# D_amp_Schem.net
KiCad netlist of a schematic drawn in Altium Designer
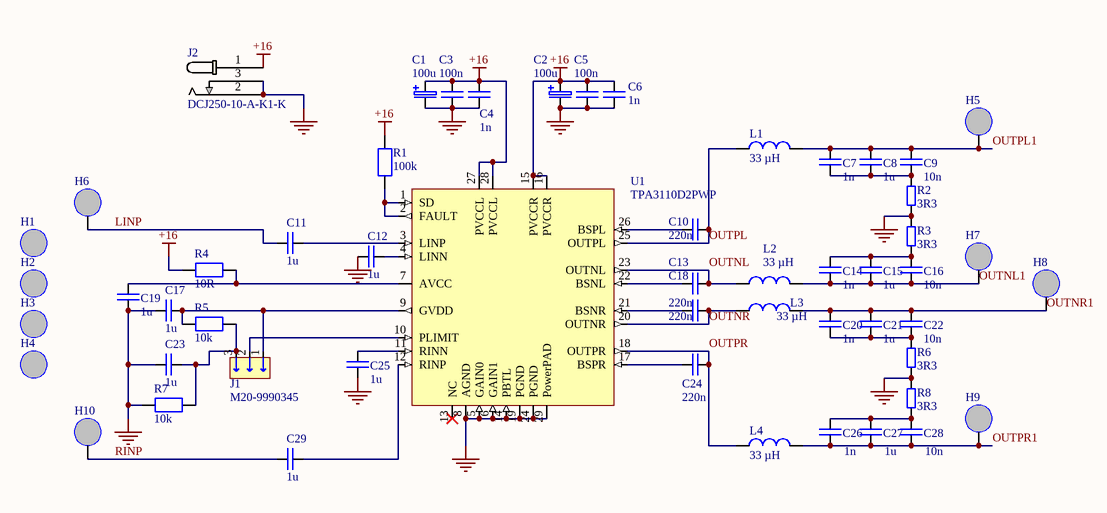
[diagram p0: D_amp_Schem.SchDoc]

(export (version "E")
  (design (tool "Eeschema 10.0.6"))
  (components
    (comp (ref "C1")
      (value "100u")
      (footprint "Cap_100u_Alum")
      (description "CAP ALUM 100UF 20% 50V SMD")
      (fields
        (field (name "MANUFACTURER") "United Chemi-Con")
        (field (name "MANUFACTURER PART NUMBER") "EMZR500ARA101MF80G")
      )
      (libsource (lib "Schematic_Library") (part "Cap_100u_Alum"))
    )
    (comp (ref "C2")
      (value "100u")
      (footprint "Cap_100u_Alum")
      (description "CAP ALUM 100UF 20% 50V SMD")
      (fields
        (field (name "MANUFACTURER") "United Chemi-Con")
        (field (name "MANUFACTURER PART NUMBER") "EMZR500ARA101MF80G")
      )
      (libsource (lib "Schematic_Library") (part "Cap_100u_Alum"))
    )
    (comp (ref "C3")
      (value "100n")
      (footprint "Cap_0603")
      (description "CAP CER 0.1UF 50V X7R 0603")
      (fields
        (field (name "MANUFACTURER") "KEMET")
        (field (name "MANUFACTURER PART NUMBER") "C0603C104K5RACTU")
      )
      (libsource (lib "Schematic_Library") (part "Cap_100n_0603_cer"))
    )
    (comp (ref "C4")
      (value "1n")
      (footprint "Cap_0603")
      (description "CAP CER 1000PF 50V X7R 0603")
      (fields
        (field (name "MANUFACTURER") "KEMET")
        (field (name "MANUFACTURER PART NUMBER") "C0603C102K5RACTU")
      )
      (libsource (lib "Schematic_Library") (part "CAP_1n_0603"))
    )
    (comp (ref "C5")
      (value "100n")
      (footprint "Cap_0603")
      (description "CAP CER 0.1UF 50V X7R 0603")
      (fields
        (field (name "MANUFACTURER") "KEMET")
        (field (name "MANUFACTURER PART NUMBER") "C0603C104K5RACTU")
      )
      (libsource (lib "Schematic_Library") (part "Cap_100n_0603_cer"))
    )
    (comp (ref "C6")
      (value "1n")
      (footprint "Cap_0603")
      (description "CAP CER 1000PF 50V X7R 0603")
      (fields
        (field (name "MANUFACTURER") "KEMET")
        (field (name "MANUFACTURER PART NUMBER") "C0603C102K5RACTU")
      )
      (libsource (lib "Schematic_Library") (part "CAP_1n_0603"))
    )
    (comp (ref "C7")
      (value "1n")
      (footprint "Cap_0603")
      (description "CAP CER 1000PF 50V X7R 0603")
      (fields
        (field (name "MANUFACTURER") "KEMET")
        (field (name "MANUFACTURER PART NUMBER") "C0603C102K5RACTU")
      )
      (libsource (lib "Schematic_Library") (part "CAP_1n_0603"))
    )
    (comp (ref "C8")
      (value "1u")
      (footprint "Cap_0603")
      (description "CAP CER 1UF 16V X7R 0603 16V")
      (fields
        (field (name "MANUFACTURER") "KEMET")
        (field (name "MANUFACTURER PART NUMBER") "C0603C105K4RACTU")
      )
      (libsource (lib "Schematic_Library") (part "Cap_1u_0603_cer"))
    )
    (comp (ref "C9")
      (value "10n")
      (footprint "Cap_0603")
      (description "CAP CER 10000PF 50V X7R 0603")
      (fields
        (field (name "MANUFACTURER") "KEMET")
        (field (name "MANUFACTURER PART NUMBER") "C0603C103K5RACTU")
      )
      (libsource (lib "Schematic_Library") (part "Cap_10n_0603_cer"))
    )
    (comp (ref "C10")
      (value "220n")
      (footprint "Cap_0603")
      (description "CAP CER 0.22UF 50V X7R 0603")
      (fields
        (field (name "MANUFACTURER") "Murata")
        (field (name "MANUFACTURER PART NUMBER") "GRM188R71H224KAC4D")
      )
      (libsource (lib "Schematic_Library") (part "Cap_220n_0603_Cer"))
    )
    (comp (ref "C11")
      (value "1u")
      (footprint "Cap_0603")
      (description "CAP CER 1UF 16V X7R 0603 16V")
      (fields
        (field (name "MANUFACTURER") "KEMET")
        (field (name "MANUFACTURER PART NUMBER") "C0603C105K4RACTU")
      )
      (libsource (lib "Schematic_Library") (part "Cap_1u_0603_cer"))
    )
    (comp (ref "C12")
      (value "1u")
      (footprint "Cap_0603")
      (description "CAP CER 1UF 16V X7R 0603 16V")
      (fields
        (field (name "MANUFACTURER") "KEMET")
        (field (name "MANUFACTURER PART NUMBER") "C0603C105K4RACTU")
      )
      (libsource (lib "Schematic_Library") (part "Cap_1u_0603_cer"))
    )
    (comp (ref "C13")
      (value "220n")
      (footprint "Cap_0603")
      (description "CAP CER 0.22UF 50V X7R 0603")
      (fields
        (field (name "MANUFACTURER") "Murata")
        (field (name "MANUFACTURER PART NUMBER") "GRM188R71H224KAC4D")
      )
      (libsource (lib "Schematic_Library") (part "Cap_220n_0603_Cer"))
    )
    (comp (ref "C14")
      (value "1n")
      (footprint "Cap_0603")
      (description "CAP CER 1000PF 50V X7R 0603")
      (fields
        (field (name "MANUFACTURER") "KEMET")
        (field (name "MANUFACTURER PART NUMBER") "C0603C102K5RACTU")
      )
      (libsource (lib "Schematic_Library") (part "CAP_1n_0603"))
    )
    (comp (ref "C15")
      (value "1u")
      (footprint "Cap_0603")
      (description "CAP CER 1UF 16V X7R 0603 16V")
      (fields
        (field (name "MANUFACTURER") "KEMET")
        (field (name "MANUFACTURER PART NUMBER") "C0603C105K4RACTU")
      )
      (libsource (lib "Schematic_Library") (part "Cap_1u_0603_cer"))
    )
    (comp (ref "C16")
      (value "10n")
      (footprint "Cap_0603")
      (description "CAP CER 10000PF 50V X7R 0603")
      (fields
        (field (name "MANUFACTURER") "KEMET")
        (field (name "MANUFACTURER PART NUMBER") "C0603C103K5RACTU")
      )
      (libsource (lib "Schematic_Library") (part "Cap_10n_0603_cer"))
    )
    (comp (ref "C17")
      (value "1u")
      (footprint "Cap_0603")
      (description "CAP CER 1UF 16V X7R 0603 16V")
      (fields
        (field (name "MANUFACTURER") "KEMET")
        (field (name "MANUFACTURER PART NUMBER") "C0603C105K4RACTU")
      )
      (libsource (lib "Schematic_Library") (part "Cap_1u_0603_cer"))
    )
    (comp (ref "C18")
      (value "220n")
      (footprint "Cap_0603")
      (description "CAP CER 0.22UF 50V X7R 0603")
      (fields
        (field (name "MANUFACTURER") "Murata")
        (field (name "MANUFACTURER PART NUMBER") "GRM188R71H224KAC4D")
      )
      (libsource (lib "Schematic_Library") (part "Cap_220n_0603_Cer"))
    )
    (comp (ref "C19")
      (value "1u")
      (footprint "Cap_0603")
      (description "CAP CER 1UF 16V X7R 0603 16V")
      (fields
        (field (name "MANUFACTURER") "KEMET")
        (field (name "MANUFACTURER PART NUMBER") "C0603C105K4RACTU")
      )
      (libsource (lib "Schematic_Library") (part "Cap_1u_0603_cer"))
    )
    (comp (ref "C20")
      (value "1n")
      (footprint "Cap_0603")
      (description "CAP CER 1000PF 50V X7R 0603")
      (fields
        (field (name "MANUFACTURER") "KEMET")
        (field (name "MANUFACTURER PART NUMBER") "C0603C102K5RACTU")
      )
      (libsource (lib "Schematic_Library") (part "CAP_1n_0603"))
    )
    (comp (ref "C21")
      (value "1u")
      (footprint "Cap_0603")
      (description "CAP CER 1UF 16V X7R 0603 16V")
      (fields
        (field (name "MANUFACTURER") "KEMET")
        (field (name "MANUFACTURER PART NUMBER") "C0603C105K4RACTU")
      )
      (libsource (lib "Schematic_Library") (part "Cap_1u_0603_cer"))
    )
    (comp (ref "C22")
      (value "10n")
      (footprint "Cap_0603")
      (description "CAP CER 10000PF 50V X7R 0603")
      (fields
        (field (name "MANUFACTURER") "KEMET")
        (field (name "MANUFACTURER PART NUMBER") "C0603C103K5RACTU")
      )
      (libsource (lib "Schematic_Library") (part "Cap_10n_0603_cer"))
    )
    (comp (ref "C23")
      (value "1u")
      (footprint "Cap_0603")
      (description "CAP CER 1UF 16V X7R 0603 16V")
      (fields
        (field (name "MANUFACTURER") "KEMET")
        (field (name "MANUFACTURER PART NUMBER") "C0603C105K4RACTU")
      )
      (libsource (lib "Schematic_Library") (part "Cap_1u_0603_cer"))
    )
    (comp (ref "C24")
      (value "220n")
      (footprint "Cap_0603")
      (description "CAP CER 0.22UF 50V X7R 0603")
      (fields
        (field (name "MANUFACTURER") "Murata")
        (field (name "MANUFACTURER PART NUMBER") "GRM188R71H224KAC4D")
      )
      (libsource (lib "Schematic_Library") (part "Cap_220n_0603_Cer"))
    )
    (comp (ref "C25")
      (value "1u")
      (footprint "Cap_0603")
      (description "CAP CER 1UF 16V X7R 0603 16V")
      (fields
        (field (name "MANUFACTURER") "KEMET")
        (field (name "MANUFACTURER PART NUMBER") "C0603C105K4RACTU")
      )
      (libsource (lib "Schematic_Library") (part "Cap_1u_0603_cer"))
    )
    (comp (ref "C26")
      (value "1n")
      (footprint "Cap_0603")
      (description "CAP CER 1000PF 50V X7R 0603")
      (fields
        (field (name "MANUFACTURER") "KEMET")
        (field (name "MANUFACTURER PART NUMBER") "C0603C102K5RACTU")
      )
      (libsource (lib "Schematic_Library") (part "CAP_1n_0603"))
    )
    (comp (ref "C27")
      (value "1u")
      (footprint "Cap_0603")
      (description "CAP CER 1UF 16V X7R 0603 16V")
      (fields
        (field (name "MANUFACTURER") "KEMET")
        (field (name "MANUFACTURER PART NUMBER") "C0603C105K4RACTU")
      )
      (libsource (lib "Schematic_Library") (part "Cap_1u_0603_cer"))
    )
    (comp (ref "C28")
      (value "10n")
      (footprint "Cap_0603")
      (description "CAP CER 10000PF 50V X7R 0603")
      (fields
        (field (name "MANUFACTURER") "KEMET")
        (field (name "MANUFACTURER PART NUMBER") "C0603C103K5RACTU")
      )
      (libsource (lib "Schematic_Library") (part "Cap_10n_0603_cer"))
    )
    (comp (ref "C29")
      (value "1u")
      (footprint "Cap_0603")
      (description "CAP CER 1UF 16V X7R 0603 16V")
      (fields
        (field (name "MANUFACTURER") "KEMET")
        (field (name "MANUFACTURER PART NUMBER") "C0603C105K4RACTU")
      )
      (libsource (lib "Schematic_Library") (part "Cap_1u_0603_cer"))
    )
    (comp (ref "H1")
      (value "Mounting_Holes_3.2")
      (footprint "Mounting_Hole_3.2mm")
      (description "Mounting Hole Non-Plated 3.2mm")
      (libsource (lib "Schematic_Library") (part "Mounting_Holes_3.2"))
    )
    (comp (ref "H2")
      (value "Mounting_Holes_3.2")
      (footprint "Mounting_Hole_3.2mm")
      (description "Mounting Hole Non-Plated 3.2mm")
      (libsource (lib "Schematic_Library") (part "Mounting_Holes_3.2"))
    )
    (comp (ref "H3")
      (value "Mounting_Holes_3.2")
      (footprint "Mounting_Hole_3.2mm")
      (description "Mounting Hole Non-Plated 3.2mm")
      (libsource (lib "Schematic_Library") (part "Mounting_Holes_3.2"))
    )
    (comp (ref "H4")
      (value "Mounting_Holes_3.2")
      (footprint "Mounting_Hole_3.2mm")
      (description "Mounting Hole Non-Plated 3.2mm")
      (libsource (lib "Schematic_Library") (part "Mounting_Holes_3.2"))
    )
    (comp (ref "H5")
      (value "Mounting_Hole_Pad_2.2")
      (footprint "Mounting_Hole_Pad_2.2")
      (libsource (lib "Schematic_Library") (part "Mounting_Hole_Pad_2.2"))
    )
    (comp (ref "H6")
      (value "Mounting_Hole_Pad_2.2")
      (footprint "Mounting_Hole_Pad_2.2")
      (libsource (lib "Schematic_Library") (part "Mounting_Hole_Pad_2.2"))
    )
    (comp (ref "H7")
      (value "Mounting_Hole_Pad_2.2")
      (footprint "Mounting_Hole_Pad_2.2")
      (libsource (lib "Schematic_Library") (part "Mounting_Hole_Pad_2.2"))
    )
    (comp (ref "H8")
      (value "Mounting_Hole_Pad_2.2")
      (footprint "Mounting_Hole_Pad_2.2")
      (libsource (lib "Schematic_Library") (part "Mounting_Hole_Pad_2.2"))
    )
    (comp (ref "H9")
      (value "Mounting_Hole_Pad_2.2")
      (footprint "Mounting_Hole_Pad_2.2")
      (libsource (lib "Schematic_Library") (part "Mounting_Hole_Pad_2.2"))
    )
    (comp (ref "H10")
      (value "Mounting_Hole_Pad_2.2")
      (footprint "Mounting_Hole_Pad_2.2")
      (libsource (lib "Schematic_Library") (part "Mounting_Hole_Pad_2.2"))
    )
    (comp (ref "J1")
      (value "M20-9990345")
      (footprint "HDR1x3")
      (description "CONN HEADER VERT 3POS 2.54MM")
      (fields (field (name "MANUFACTURER") "Harwin"))
      (libsource (lib "Schematic_Library") (part "M20-9990345"))
    )
    (comp (ref "J2")
      (value "DCJ250-10-A-K1-K")
      (footprint "DCJ250-10-A-K1-K")
      (description "DCJ250 Series 20 V 5 A 2 Conductors/3 Contacts Horizontal Through Hole DC Power Jack")
      (fields (field (name "MANUFACTURER") "Global Connector Technology"))
      (libsource (lib "Schematic_Library") (part "DCJ250-10-A-K1-K"))
    )
    (comp (ref "L1")
      (value "33 µH")
      (footprint "DR127-330-R")
      (description "FIXED IND 33UH 3.23A 60 MOHM SMD")
      (fields (field (name "MANUFACTURER") "Eaton") (field (name "MANUFACTURER PART NUMBER") "DR127-330-R"))
      (libsource (lib "Schematic_Library") (part "Ind_33 µH"))
    )
    (comp (ref "L2")
      (value "33 µH")
      (footprint "DR127-330-R")
      (description "FIXED IND 33UH 3.23A 60 MOHM SMD")
      (fields (field (name "MANUFACTURER") "Eaton") (field (name "MANUFACTURER PART NUMBER") "DR127-330-R"))
      (libsource (lib "Schematic_Library") (part "Ind_33 µH"))
    )
    (comp (ref "L3")
      (value "33 µH")
      (footprint "DR127-330-R")
      (description "FIXED IND 33UH 3.23A 60 MOHM SMD")
      (fields (field (name "MANUFACTURER") "Eaton") (field (name "MANUFACTURER PART NUMBER") "DR127-330-R"))
      (libsource (lib "Schematic_Library") (part "Ind_33 µH"))
    )
    (comp (ref "L4")
      (value "33 µH")
      (footprint "DR127-330-R")
      (description "FIXED IND 33UH 3.23A 60 MOHM SMD")
      (fields (field (name "MANUFACTURER") "Eaton") (field (name "MANUFACTURER PART NUMBER") "DR127-330-R"))
      (libsource (lib "Schematic_Library") (part "Ind_33 µH"))
    )
    (comp (ref "R1")
      (value "100k")
      (footprint "Res_0603")
      (description "RES 100K OHM 1% 1/10W 0603")
      (fields
        (field (name "MANUFACTURER") "Yageo Group")
        (field (name "MANUFACTURER PART NUMBER") "RC0603FR-07100KL")
      )
      (libsource (lib "Schematic_Library") (part "Res_100K_0603"))
    )
    (comp (ref "R2")
      (value "3R3")
      (footprint "Res_0603")
      (description "RES SMD 3.3 OHM 1% 1/8W 0603")
      (fields
        (field (name "MANUFACTURER") "Vishay")
        (field (name "MANUFACTURER PART NUMBER") "CRCW06033R30FKEA")
      )
      (libsource (lib "Schematic_Library") (part "Res_3R3_0603"))
    )
    (comp (ref "R3")
      (value "3R3")
      (footprint "Res_0603")
      (description "RES SMD 3.3 OHM 1% 1/8W 0603")
      (fields
        (field (name "MANUFACTURER") "Vishay")
        (field (name "MANUFACTURER PART NUMBER") "CRCW06033R30FKEA")
      )
      (libsource (lib "Schematic_Library") (part "Res_3R3_0603"))
    )
    (comp (ref "R4")
      (value "10R")
      (footprint "Res_0603")
      (description "RES 10 OHM 1% 1/10W 0603")
      (fields
        (field (name "MANUFACTURER") "Yageo Group")
        (field (name "MANUFACTURER PART NUMBER") "RC0603FR-0710RL")
      )
      (libsource (lib "Schematic_Library") (part "Res_10_0603"))
    )
    (comp (ref "R5")
      (value "10k")
      (footprint "Res_0603")
      (description "RES 10K OHM 1% 1/10W 0603")
      (fields
        (field (name "MANUFACTURER") "Yageo Group")
        (field (name "MANUFACTURER PART NUMBER") "RC0603FR-0710KL")
      )
      (libsource (lib "Schematic_Library") (part "Res_10k_0603"))
    )
    (comp (ref "R6")
      (value "3R3")
      (footprint "Res_0603")
      (description "RES SMD 3.3 OHM 1% 1/8W 0603")
      (fields
        (field (name "MANUFACTURER") "Vishay")
        (field (name "MANUFACTURER PART NUMBER") "CRCW06033R30FKEA")
      )
      (libsource (lib "Schematic_Library") (part "Res_3R3_0603"))
    )
    (comp (ref "R7")
      (value "10k")
      (footprint "Res_0603")
      (description "RES 10K OHM 1% 1/10W 0603")
      (fields
        (field (name "MANUFACTURER") "Yageo Group")
        (field (name "MANUFACTURER PART NUMBER") "RC0603FR-0710KL")
      )
      (libsource (lib "Schematic_Library") (part "Res_10k_0603"))
    )
    (comp (ref "R8")
      (value "3R3")
      (footprint "Res_0603")
      (description "RES SMD 3.3 OHM 1% 1/8W 0603")
      (fields
        (field (name "MANUFACTURER") "Vishay")
        (field (name "MANUFACTURER PART NUMBER") "CRCW06033R30FKEA")
      )
      (libsource (lib "Schematic_Library") (part "Res_3R3_0603"))
    )
    (comp (ref "U1")
      (value "TPA3110D2PWP")
      (footprint "TPA3110D2_15_W")
      (description "Audio Amp Speaker 2-CH Stereo 15W Class-D 28-Pin HTSSOP EP Tube")
      (fields (field (name "MANUFACTURER") "Texas Instruments"))
      (libsource (lib "Schematic_Library") (part "TPA3110D2PWP"))
    )
  )
  (nets
    (net (code "1") (name "+16") (class "Default")
      (node (ref "C1") (pin "1") (pintype "passive"))
      (node (ref "C2") (pin "1") (pintype "passive"))
      (node (ref "C3") (pin "2") (pintype "passive"))
      (node (ref "C4") (pin "2") (pintype "passive"))
      (node (ref "C5") (pin "2") (pintype "passive"))
      (node (ref "C6") (pin "2") (pintype "passive"))
      (node (ref "J2") (pin "1") (pinfunction "1_1") (pintype "passive"))
      (node (ref "R1") (pin "2") (pintype "passive"))
      (node (ref "R4") (pin "1") (pintype "passive"))
      (node (ref "U1") (pin "15") (pinfunction "PVCCR_15") (pintype "power_in"))
      (node (ref "U1") (pin "16") (pinfunction "PVCCR_16") (pintype "power_in"))
      (node (ref "U1") (pin "27") (pinfunction "PVCCL_27") (pintype "power_in"))
      (node (ref "U1") (pin "28") (pinfunction "PVCCL_28") (pintype "power_in"))
    )
    (net (code "2") (name "/LINP") (class "Default")
      (node (ref "C11") (pin "1") (pintype "passive"))
      (node (ref "H6") (pin "1") (pintype "passive"))
    )
    (net (code "3") (name "/OUTNL") (class "Default")
      (node (ref "C13") (pin "2") (pintype "passive"))
      (node (ref "L2") (pin "1") (pintype "passive"))
      (node (ref "U1") (pin "23") (pinfunction "OUTNL_23") (pintype "output"))
    )
    (net (code "4") (name "/OUTNL1") (class "Default")
      (node (ref "C14") (pin "1") (pintype "passive"))
      (node (ref "C15") (pin "1") (pintype "passive"))
      (node (ref "C16") (pin "2") (pintype "passive"))
      (node (ref "H7") (pin "1") (pintype "passive"))
      (node (ref "L2") (pin "2") (pintype "passive"))
    )
    (net (code "5") (name "/OUTNR") (class "Default")
      (node (ref "C18") (pin "2") (pintype "passive"))
      (node (ref "L3") (pin "1") (pintype "passive"))
      (node (ref "U1") (pin "20") (pinfunction "OUTNR_20") (pintype "output"))
    )
    (net (code "6") (name "/OUTNR1") (class "Default")
      (node (ref "C20") (pin "2") (pintype "passive"))
      (node (ref "C21") (pin "2") (pintype "passive"))
      (node (ref "C22") (pin "1") (pintype "passive"))
      (node (ref "H8") (pin "1") (pintype "passive"))
      (node (ref "L3") (pin "2") (pintype "passive"))
    )
    (net (code "7") (name "/OUTPL") (class "Default")
      (node (ref "C10") (pin "2") (pintype "passive"))
      (node (ref "L1") (pin "1") (pintype "passive"))
      (node (ref "U1") (pin "25") (pinfunction "OUTPL_25") (pintype "output"))
    )
    (net (code "8") (name "/OUTPL1") (class "Default")
      (node (ref "C7") (pin "2") (pintype "passive"))
      (node (ref "C8") (pin "2") (pintype "passive"))
      (node (ref "C9") (pin "1") (pintype "passive"))
      (node (ref "H5") (pin "1") (pintype "passive"))
      (node (ref "L1") (pin "2") (pintype "passive"))
    )
    (net (code "9") (name "/OUTPR") (class "Default")
      (node (ref "C24") (pin "2") (pintype "passive"))
      (node (ref "L4") (pin "1") (pintype "passive"))
      (node (ref "U1") (pin "18") (pinfunction "OUTPR_18") (pintype "output"))
    )
    (net (code "10") (name "/OUTPR1") (class "Default")
      (node (ref "C26") (pin "1") (pintype "passive"))
      (node (ref "C27") (pin "1") (pintype "passive"))
      (node (ref "C28") (pin "2") (pintype "passive"))
      (node (ref "H9") (pin "1") (pintype "passive"))
      (node (ref "L4") (pin "2") (pintype "passive"))
    )
    (net (code "11") (name "/RINP") (class "Default")
      (node (ref "C29") (pin "1") (pintype "passive"))
      (node (ref "H10") (pin "1") (pintype "passive"))
    )
    (net (code "12") (name "GND") (class "Default")
      (node (ref "C1") (pin "2") (pintype "passive"))
      (node (ref "C12") (pin "1") (pintype "passive"))
      (node (ref "C17") (pin "1") (pintype "passive"))
      (node (ref "C19") (pin "1") (pintype "passive"))
      (node (ref "C2") (pin "2") (pintype "passive"))
      (node (ref "C23") (pin "1") (pintype "passive"))
      (node (ref "C25") (pin "1") (pintype "passive"))
      (node (ref "C3") (pin "1") (pintype "passive"))
      (node (ref "C4") (pin "1") (pintype "passive"))
      (node (ref "C5") (pin "1") (pintype "passive"))
      (node (ref "C6") (pin "1") (pintype "passive"))
      (node (ref "J2") (pin "2") (pinfunction "2_2") (pintype "passive"))
      (node (ref "J2") (pin "3") (pinfunction "3_3") (pintype "passive"))
      (node (ref "R2") (pin "1") (pintype "passive"))
      (node (ref "R3") (pin "2") (pintype "passive"))
      (node (ref "R6") (pin "1") (pintype "passive"))
      (node (ref "R7") (pin "1") (pintype "passive"))
      (node (ref "R8") (pin "2") (pintype "passive"))
      (node (ref "U1") (pin "14") (pinfunction "PBTL_14") (pintype "input"))
      (node (ref "U1") (pin "19") (pinfunction "PGND_19") (pintype "passive"))
      (node (ref "U1") (pin "24") (pinfunction "PGND_24") (pintype "passive"))
      (node (ref "U1") (pin "29") (pinfunction "PowerPAD_29") (pintype "power_in"))
      (node (ref "U1") (pin "5") (pinfunction "GAIN0_5") (pintype "input"))
      (node (ref "U1") (pin "6") (pinfunction "GAIN1_6") (pintype "input"))
      (node (ref "U1") (pin "8") (pinfunction "AGND_8") (pintype "passive"))
    )
    (net (code "13") (name "Net-(C7-Pad1)") (class "Default")
      (node (ref "C7") (pin "1") (pintype "passive"))
      (node (ref "C8") (pin "1") (pintype "passive"))
      (node (ref "C9") (pin "2") (pintype "passive"))
      (node (ref "R2") (pin "2") (pintype "passive"))
    )
    (net (code "14") (name "Net-(C14-Pad2)") (class "Default")
      (node (ref "C14") (pin "2") (pintype "passive"))
      (node (ref "C15") (pin "2") (pintype "passive"))
      (node (ref "C16") (pin "1") (pintype "passive"))
      (node (ref "R3") (pin "1") (pintype "passive"))
    )
    (net (code "15") (name "Net-(C20-Pad1)") (class "Default")
      (node (ref "C20") (pin "1") (pintype "passive"))
      (node (ref "C21") (pin "1") (pintype "passive"))
      (node (ref "C22") (pin "2") (pintype "passive"))
      (node (ref "R6") (pin "2") (pintype "passive"))
    )
    (net (code "16") (name "Net-(C23-Pad2)") (class "Default")
      (node (ref "C23") (pin "2") (pintype "passive"))
      (node (ref "J1") (pin "3") (pintype "passive"))
      (node (ref "R5") (pin "2") (pintype "passive"))
      (node (ref "R7") (pin "2") (pintype "passive"))
    )
    (net (code "17") (name "Net-(C26-Pad2)") (class "Default")
      (node (ref "C26") (pin "2") (pintype "passive"))
      (node (ref "C27") (pin "2") (pintype "passive"))
      (node (ref "C28") (pin "1") (pintype "passive"))
      (node (ref "R8") (pin "1") (pintype "passive"))
    )
    (net (code "18") (name "Net-(U1-AVCC)") (class "Default")
      (node (ref "C19") (pin "2") (pintype "passive"))
      (node (ref "R4") (pin "2") (pintype "passive"))
      (node (ref "U1") (pin "7") (pinfunction "AVCC_7") (pintype "power_in"))
    )
    (net (code "19") (name "Net-(U1-BSNL)") (class "Default")
      (node (ref "C13") (pin "1") (pintype "passive"))
      (node (ref "U1") (pin "22") (pinfunction "BSNL_22") (pintype "input"))
    )
    (net (code "20") (name "Net-(U1-BSNR)") (class "Default")
      (node (ref "C18") (pin "1") (pintype "passive"))
      (node (ref "U1") (pin "21") (pinfunction "BSNR_21") (pintype "input"))
    )
    (net (code "21") (name "Net-(U1-BSPL)") (class "Default")
      (node (ref "C10") (pin "1") (pintype "passive"))
      (node (ref "U1") (pin "26") (pinfunction "BSPL_26") (pintype "input"))
    )
    (net (code "22") (name "Net-(U1-BSPR)") (class "Default")
      (node (ref "C24") (pin "1") (pintype "passive"))
      (node (ref "U1") (pin "17") (pinfunction "BSPR_17") (pintype "input"))
    )
    (net (code "23") (name "Net-(U1-FAULT)") (class "Default")
      (node (ref "R1") (pin "1") (pintype "passive"))
      (node (ref "U1") (pin "1") (pinfunction "SD_1") (pintype "input"))
      (node (ref "U1") (pin "2") (pinfunction "FAULT_2") (pintype "output"))
    )
    (net (code "24") (name "Net-(U1-GVDD)") (class "Default")
      (node (ref "C17") (pin "2") (pintype "passive"))
      (node (ref "J1") (pin "1") (pintype "passive"))
      (node (ref "R5") (pin "1") (pintype "passive"))
      (node (ref "U1") (pin "9") (pinfunction "GVDD_9") (pintype "output"))
    )
    (net (code "25") (name "Net-(U1-LINN)") (class "Default")
      (node (ref "C12") (pin "2") (pintype "passive"))
      (node (ref "U1") (pin "4") (pinfunction "LINN_4") (pintype "input"))
    )
    (net (code "26") (name "Net-(U1-LINP)") (class "Default")
      (node (ref "C11") (pin "2") (pintype "passive"))
      (node (ref "U1") (pin "3") (pinfunction "LINP_3") (pintype "input"))
    )
    (net (code "27") (name "Net-(U1-PLIMIT)") (class "Default")
      (node (ref "J1") (pin "2") (pintype "passive"))
      (node (ref "U1") (pin "10") (pinfunction "PLIMIT_10") (pintype "input"))
    )
    (net (code "28") (name "Net-(U1-RINN)") (class "Default")
      (node (ref "C25") (pin "2") (pintype "passive"))
      (node (ref "U1") (pin "11") (pinfunction "RINN_11") (pintype "input"))
    )
    (net (code "29") (name "Net-(U1-RINP)") (class "Default")
      (node (ref "C29") (pin "2") (pintype "passive"))
      (node (ref "U1") (pin "12") (pinfunction "RINP_12") (pintype "input"))
    )
    (net (code "30") (name "unconnected-(U1-NC-Pad13)") (class "Default")
      (node (ref "U1") (pin "13") (pinfunction "NC_13") (pintype "passive+no_connect"))
    )
  )
)
